# Schema_Electronique_Bracelet.net
KiCad netlist of a schematic drawn in EAGLE
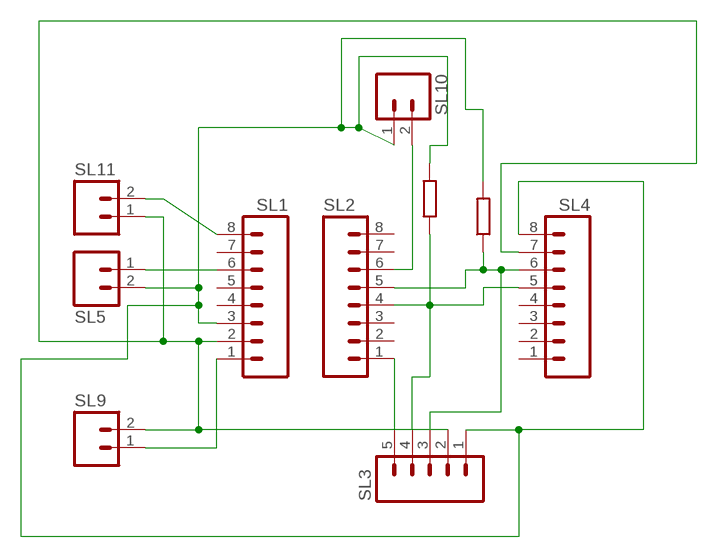
[diagram p0: schematic, sheet 1]

(export (version "E")
  (design (tool "Eeschema 10.0.6"))
  (components
    (comp (ref "SL1")
      (value "ESP32_LEFT")
      (footprint "eagle-import:08PA")
      (libsource (lib "eagle-import") (part "MA08"))
    )
    (comp (ref "SL2")
      (value "ESP32_RIGHT")
      (footprint "eagle-import:08PA")
      (libsource (lib "eagle-import") (part "MA08"))
    )
    (comp (ref "SL3")
      (value "MAX30102")
      (footprint "eagle-import:05PA")
      (libsource (lib "eagle-import") (part "MA05"))
    )
    (comp (ref "SL4")
      (value "MPU6050")
      (footprint "eagle-import:08PA")
      (libsource (lib "eagle-import") (part "MA08"))
    )
    (comp (ref "SL5")
      (value "BUZZER")
      (footprint "eagle-import:02PA")
      (libsource (lib "eagle-import") (part "MA02"))
    )
    (comp (ref "SL9")
      (value "ON_OFF_SWITCH")
      (footprint "eagle-import:02PA")
      (libsource (lib "eagle-import") (part "MA02"))
    )
    (comp (ref "SL10")
      (value "POWER_INPUT")
      (footprint "eagle-import:02PA")
      (libsource (lib "eagle-import") (part "MA02"))
    )
    (comp (ref "SL11")
      (value "POWER_INPUT")
      (footprint "eagle-import:02PA")
      (libsource (lib "eagle-import") (part "MA02"))
    )
  )
  (nets
    (net (code "1") (name "Net-(SL1-Pad1)") (class "Default")
      (node (ref "SL1") (pin "1") (pinfunction "1_1") (pintype "passive"))
      (node (ref "SL9") (pin "1") (pinfunction "1_1") (pintype "passive"))
    )
    (net (code "2") (name "Net-(SL1-Pad2)") (class "Default")
      (node (ref "SL1") (pin "2") (pinfunction "2_2") (pintype "passive"))
      (node (ref "SL11") (pin "1") (pinfunction "1_1") (pintype "passive"))
      (node (ref "SL3") (pin "2") (pinfunction "2_2") (pintype "passive"))
      (node (ref "SL4") (pin "7") (pinfunction "7_7") (pintype "passive"))
      (node (ref "SL9") (pin "2") (pinfunction "2_2") (pintype "passive"))
    )
    (net (code "3") (name "Net-(SL1-Pad3)") (class "Default")
      (node (ref "SL1") (pin "3") (pinfunction "3_3") (pintype "passive"))
      (node (ref "SL10") (pin "1") (pinfunction "1_1") (pintype "passive"))
      (node (ref "SL3") (pin "1") (pinfunction "1_1") (pintype "passive"))
      (node (ref "SL4") (pin "8") (pinfunction "8_8") (pintype "passive"))
      (node (ref "SL5") (pin "2") (pinfunction "2_2") (pintype "passive"))
    )
    (net (code "4") (name "Net-(SL1-Pad6)") (class "Default")
      (node (ref "SL1") (pin "6") (pinfunction "6_6") (pintype "passive"))
      (node (ref "SL5") (pin "1") (pinfunction "1_1") (pintype "passive"))
    )
    (net (code "5") (name "Net-(SL1-Pad8)") (class "Default")
      (node (ref "SL1") (pin "8") (pinfunction "8_8") (pintype "passive"))
      (node (ref "SL11") (pin "2") (pinfunction "2_2") (pintype "passive"))
    )
    (net (code "6") (name "Net-(SL2-Pad1)") (class "Default")
      (node (ref "SL2") (pin "1") (pinfunction "1_1") (pintype "passive"))
      (node (ref "SL3") (pin "5") (pinfunction "5_5") (pintype "passive"))
    )
    (net (code "7") (name "Net-(SL2-Pad4)") (class "Default")
      (node (ref "SL2") (pin "4") (pinfunction "4_4") (pintype "passive"))
      (node (ref "SL3") (pin "4") (pinfunction "4_4") (pintype "passive"))
      (node (ref "SL4") (pin "5") (pinfunction "5_5") (pintype "passive"))
    )
    (net (code "8") (name "Net-(SL2-Pad5)") (class "Default")
      (node (ref "SL2") (pin "5") (pinfunction "5_5") (pintype "passive"))
      (node (ref "SL3") (pin "3") (pinfunction "3_3") (pintype "passive"))
      (node (ref "SL4") (pin "6") (pinfunction "6_6") (pintype "passive"))
    )
    (net (code "9") (name "Net-(SL10-Pad2)") (class "Default")
      (node (ref "SL10") (pin "2") (pinfunction "2_2") (pintype "passive"))
      (node (ref "SL2") (pin "6") (pinfunction "6_6") (pintype "passive"))
    )
    (net (code "10") (name "unconnected-(SL1-Pad4)") (class "Default")
      (node (ref "SL1") (pin "4") (pinfunction "4_4") (pintype "passive"))
    )
    (net (code "11") (name "unconnected-(SL1-Pad5)") (class "Default")
      (node (ref "SL1") (pin "5") (pinfunction "5_5") (pintype "passive"))
    )
    (net (code "12") (name "unconnected-(SL1-Pad7)") (class "Default")
      (node (ref "SL1") (pin "7") (pinfunction "7_7") (pintype "passive"))
    )
    (net (code "13") (name "unconnected-(SL2-Pad2)") (class "Default")
      (node (ref "SL2") (pin "2") (pinfunction "2_2") (pintype "passive"))
    )
    (net (code "14") (name "unconnected-(SL2-Pad3)") (class "Default")
      (node (ref "SL2") (pin "3") (pinfunction "3_3") (pintype "passive"))
    )
    (net (code "15") (name "unconnected-(SL2-Pad7)") (class "Default")
      (node (ref "SL2") (pin "7") (pinfunction "7_7") (pintype "passive"))
    )
    (net (code "16") (name "unconnected-(SL2-Pad8)") (class "Default")
      (node (ref "SL2") (pin "8") (pinfunction "8_8") (pintype "passive"))
    )
    (net (code "17") (name "unconnected-(SL4-Pad1)") (class "Default")
      (node (ref "SL4") (pin "1") (pinfunction "1_1") (pintype "passive"))
    )
    (net (code "18") (name "unconnected-(SL4-Pad2)") (class "Default")
      (node (ref "SL4") (pin "2") (pinfunction "2_2") (pintype "passive"))
    )
    (net (code "19") (name "unconnected-(SL4-Pad3)") (class "Default")
      (node (ref "SL4") (pin "3") (pinfunction "3_3") (pintype "passive"))
    )
    (net (code "20") (name "unconnected-(SL4-Pad4)") (class "Default")
      (node (ref "SL4") (pin "4") (pinfunction "4_4") (pintype "passive"))
    )
  )
)
